# BrushBotComm_C3.net
KiCad netlist of a schematic drawn in EAGLE
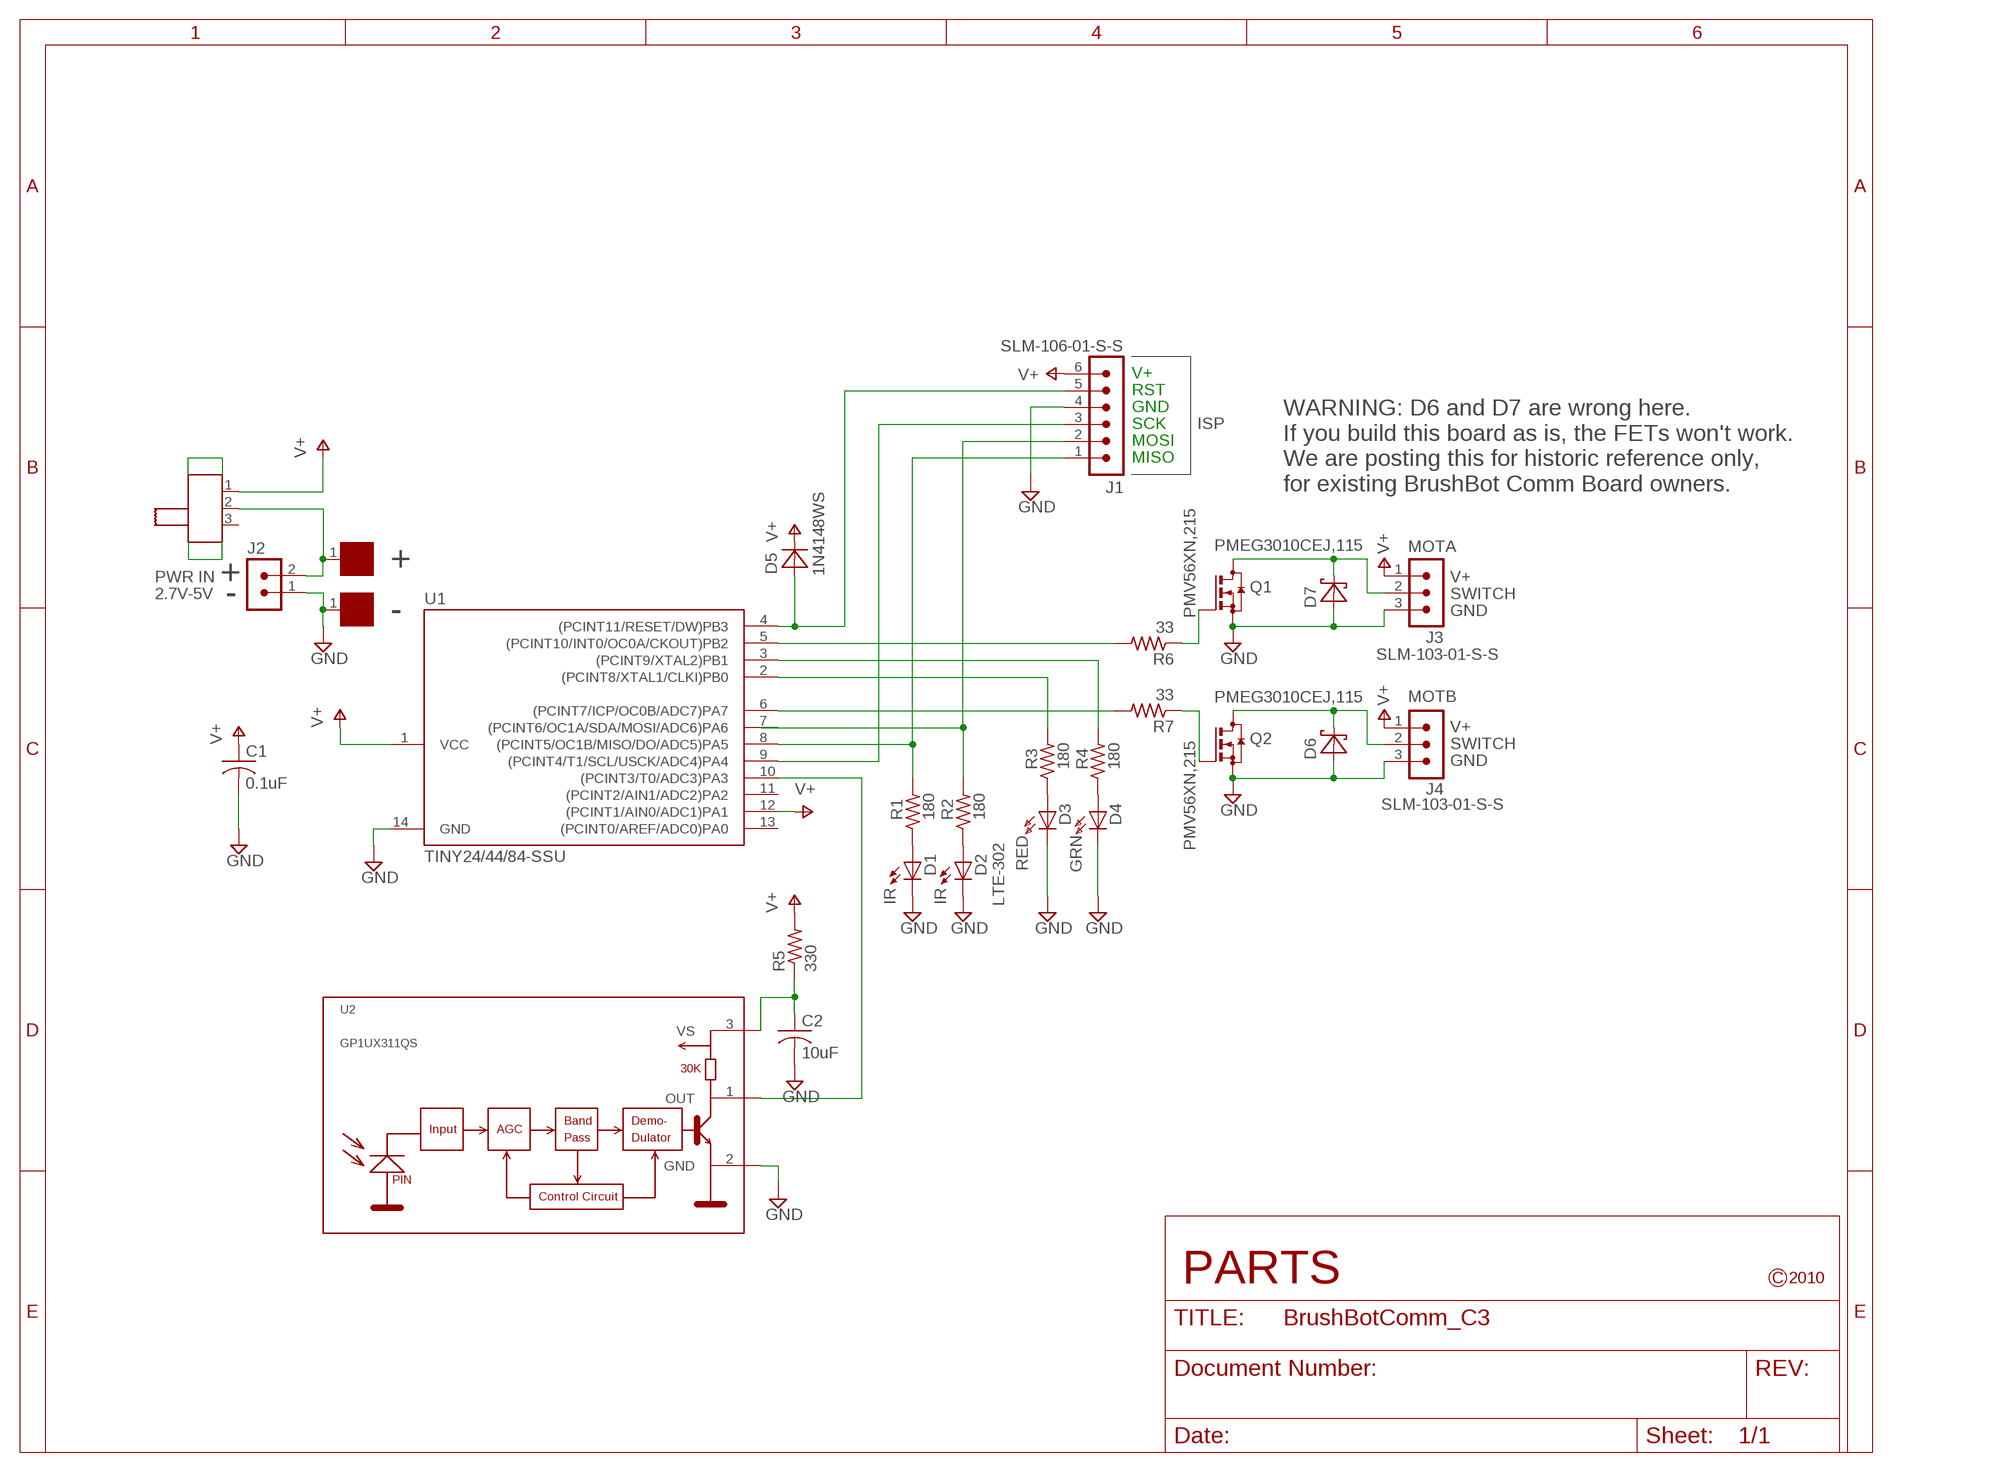
[diagram p0: schematic, sheet 1]

(export (version "E")
  (design (tool "Eeschema 10.0.6"))
  (components
    (comp (ref "+")
      (value "BATTERM4X4MM")
      (footprint "eagle-import:BATTERM")
      (libsource (lib "eagle-import") (part "BATTERM4X4MM"))
    )
    (comp (ref "-")
      (value "BATTERM4X4MM")
      (footprint "eagle-import:BATTERM")
      (libsource (lib "eagle-import") (part "BATTERM4X4MM"))
    )
    (comp (ref "C1")
      (value "0.1uF")
      (footprint "eagle-import:C0603")
      (libsource (lib "eagle-import") (part "C-USC0603"))
    )
    (comp (ref "C2")
      (value "10uF")
      (footprint "eagle-import:C1206")
      (libsource (lib "eagle-import") (part "C-USC1206"))
    )
    (comp (ref "D1")
      (value "LTE-302")
      (footprint "eagle-import:IRL80A")
      (libsource (lib "eagle-import") (part "LEDIRL80A"))
    )
    (comp (ref "D2")
      (value "LTE-302")
      (footprint "eagle-import:IRL80A")
      (libsource (lib "eagle-import") (part "LEDIRL80A"))
    )
    (comp (ref "D3")
      (value "RED")
      (footprint "eagle-import:LED603")
      (libsource (lib "eagle-import") (part "LED603"))
    )
    (comp (ref "D4")
      (value "GRN")
      (footprint "eagle-import:LED603")
      (libsource (lib "eagle-import") (part "LED603"))
    )
    (comp (ref "D5")
      (value "1N4148WS")
      (footprint "eagle-import:SOD323-R")
      (libsource (lib "eagle-import") (part "DIODE-SOD323-RE"))
    )
    (comp (ref "D6")
      (value "PMEG3010CEJ,115")
      (footprint "eagle-import:SOD323-R")
      (libsource (lib "eagle-import") (part "SCHOTTKYSOD323"))
    )
    (comp (ref "D7")
      (value "PMEG3010CEJ,115")
      (footprint "eagle-import:SOD323-R")
      (libsource (lib "eagle-import") (part "SCHOTTKYSOD323"))
    )
    (comp (ref "J1")
      (value "SLM-106-01-S-S")
      (footprint "eagle-import:MA06O-1-25")
      (libsource (lib "eagle-import") (part "MA06-1OCTPADS"))
    )
    (comp (ref "J2")
      (value "MA02-1OCTPADS")
      (footprint "eagle-import:MA02O-1")
      (libsource (lib "eagle-import") (part "MA02-1OCTPADS"))
    )
    (comp (ref "J3")
      (value "SLM-103-01-S-S")
      (footprint "eagle-import:MA03O-1-25")
      (libsource (lib "eagle-import") (part "MA03-1OCTPADS-25"))
    )
    (comp (ref "J4")
      (value "SLM-103-01-S-S")
      (footprint "eagle-import:MA03O-1-25")
      (libsource (lib "eagle-import") (part "MA03-1OCTPADS-25"))
    )
    (comp (ref "PWR")
      (value "SSSS811101")
      (footprint "eagle-import:SSSS8")
      (libsource (lib "eagle-import") (part "SSSS8"))
    )
    (comp (ref "Q1")
      (value "PMV56XN,215")
      (footprint "eagle-import:SOT23")
      (libsource (lib "eagle-import") (part "BSS123"))
    )
    (comp (ref "Q2")
      (value "PMV56XN,215")
      (footprint "eagle-import:SOT23")
      (libsource (lib "eagle-import") (part "BSS123"))
    )
    (comp (ref "R1")
      (value "180")
      (footprint "eagle-import:R0603")
      (libsource (lib "eagle-import") (part "R-US_R0603"))
    )
    (comp (ref "R2")
      (value "180")
      (footprint "eagle-import:R0603")
      (libsource (lib "eagle-import") (part "R-US_R0603"))
    )
    (comp (ref "R3")
      (value "180")
      (footprint "eagle-import:R0603")
      (libsource (lib "eagle-import") (part "R-US_R0603"))
    )
    (comp (ref "R4")
      (value "180")
      (footprint "eagle-import:R0603")
      (libsource (lib "eagle-import") (part "R-US_R0603"))
    )
    (comp (ref "R5")
      (value "330")
      (footprint "eagle-import:R0603")
      (libsource (lib "eagle-import") (part "R-US_R0603"))
    )
    (comp (ref "R6")
      (value "33")
      (footprint "eagle-import:R0603")
      (libsource (lib "eagle-import") (part "R-US_R0603"))
    )
    (comp (ref "R7")
      (value "33")
      (footprint "eagle-import:R0603")
      (libsource (lib "eagle-import") (part "R-US_R0603"))
    )
    (comp (ref "U1")
      (value "TINY24/44/84-SSU")
      (footprint "eagle-import:SOIC14")
      (libsource (lib "eagle-import") (part "TINY24/44/84-SSU"))
    )
    (comp (ref "U2")
      (value "GP1UX311QS")
      (footprint "eagle-import:TSOP348")
      (libsource (lib "eagle-import") (part "TSOP34830"))
    )
  )
  (nets
    (net (code "1") (name "GND") (class "Default")
      (node (ref "-") (pin "1") (pinfunction "1_1") (pintype "power_in"))
      (node (ref "C1") (pin "2") (pinfunction "2_2") (pintype "passive"))
      (node (ref "C2") (pin "2") (pinfunction "2_2") (pintype "passive"))
      (node (ref "D1") (pin "K") (pinfunction "C_K") (pintype "passive"))
      (node (ref "D2") (pin "K") (pinfunction "C_K") (pintype "passive"))
      (node (ref "D3") (pin "C") (pinfunction "C_C") (pintype "passive"))
      (node (ref "D4") (pin "C") (pinfunction "C_C") (pintype "passive"))
      (node (ref "D6") (pin "A") (pinfunction "A_A") (pintype "passive"))
      (node (ref "D7") (pin "A") (pinfunction "A_A") (pintype "passive"))
      (node (ref "J1") (pin "4") (pinfunction "4_4") (pintype "passive"))
      (node (ref "J2") (pin "1") (pinfunction "1_1") (pintype "passive"))
      (node (ref "J3") (pin "3") (pinfunction "3_3") (pintype "passive"))
      (node (ref "J4") (pin "3") (pinfunction "3_3") (pintype "passive"))
      (node (ref "Q1") (pin "2") (pinfunction "S_2") (pintype "passive"))
      (node (ref "Q2") (pin "2") (pinfunction "S_2") (pintype "passive"))
      (node (ref "U1") (pin "14") (pinfunction "GND_14") (pintype "power_in"))
      (node (ref "U2") (pin "2") (pinfunction "GND_2") (pintype "power_in"))
    )
    (net (code "2") (name "Net-(+-Pad1)") (class "Default")
      (node (ref "+") (pin "1") (pinfunction "1_1") (pintype "power_in"))
      (node (ref "J2") (pin "2") (pinfunction "2_2") (pintype "passive"))
      (node (ref "PWR") (pin "2") (pinfunction "2_2") (pintype "bidirectional"))
    )
    (net (code "3") (name "Net-(D1-PadA)") (class "Default")
      (node (ref "D1") (pin "A") (pinfunction "A_A") (pintype "passive"))
      (node (ref "R1") (pin "1") (pinfunction "1_1") (pintype "passive"))
    )
    (net (code "4") (name "Net-(D2-PadA)") (class "Default")
      (node (ref "D2") (pin "A") (pinfunction "A_A") (pintype "passive"))
      (node (ref "R2") (pin "1") (pinfunction "1_1") (pintype "passive"))
    )
    (net (code "5") (name "Net-(D3-PadA)") (class "Default")
      (node (ref "D3") (pin "A") (pinfunction "A_A") (pintype "passive"))
      (node (ref "R3") (pin "1") (pinfunction "1_1") (pintype "passive"))
    )
    (net (code "6") (name "Net-(D4-PadA)") (class "Default")
      (node (ref "D4") (pin "A") (pinfunction "A_A") (pintype "passive"))
      (node (ref "R4") (pin "1") (pinfunction "1_1") (pintype "passive"))
    )
    (net (code "7") (name "Net-(PWR-PadG1)") (class "Default")
      (node (ref "PWR") (pin "G1") (pinfunction "G1_G1") (pintype "bidirectional"))
      (node (ref "PWR") (pin "G2") (pinfunction "G2_G2") (pintype "bidirectional"))
    )
    (net (code "8") (name "Net-(PWR-PadG3)") (class "Default")
      (node (ref "PWR") (pin "G3") (pinfunction "G3_G3") (pintype "bidirectional"))
      (node (ref "PWR") (pin "G4") (pinfunction "G4_G4") (pintype "bidirectional"))
    )
    (net (code "9") (name "Net-(Q1-D)") (class "Default")
      (node (ref "D7") (pin "C") (pinfunction "C_C") (pintype "passive"))
      (node (ref "J3") (pin "2") (pinfunction "2_2") (pintype "passive"))
      (node (ref "Q1") (pin "3") (pinfunction "D_3") (pintype "passive"))
    )
    (net (code "10") (name "Net-(Q1-G)") (class "Default")
      (node (ref "Q1") (pin "1") (pinfunction "G_1") (pintype "passive"))
      (node (ref "R6") (pin "1") (pinfunction "1_1") (pintype "passive"))
    )
    (net (code "11") (name "Net-(Q2-D)") (class "Default")
      (node (ref "D6") (pin "C") (pinfunction "C_C") (pintype "passive"))
      (node (ref "J4") (pin "2") (pinfunction "2_2") (pintype "passive"))
      (node (ref "Q2") (pin "3") (pinfunction "D_3") (pintype "passive"))
    )
    (net (code "12") (name "Net-(Q2-G)") (class "Default")
      (node (ref "Q2") (pin "1") (pinfunction "G_1") (pintype "passive"))
      (node (ref "R7") (pin "1") (pinfunction "1_1") (pintype "passive"))
    )
    (net (code "13") (name "Net-(U1-(PCINT3{slash}T0{slash}ADC3)PA3)") (class "Default")
      (node (ref "U1") (pin "10") (pinfunction "(PCINT3/T0/ADC3)PA3_10") (pintype "bidirectional"))
      (node (ref "U2") (pin "1") (pinfunction "OUT_1") (pintype "output"))
    )
    (net (code "14") (name "Net-(U1-(PCINT4{slash}T1{slash}SCL{slash}USCK{slash}ADC4)PA4)") (class "Default")
      (node (ref "J1") (pin "3") (pinfunction "3_3") (pintype "passive"))
      (node (ref "U1") (pin "9") (pinfunction "(PCINT4/T1/SCL/USCK/ADC4)PA4_9") (pintype "bidirectional"))
    )
    (net (code "15") (name "Net-(U1-(PCINT5{slash}OC1B{slash}MISO{slash}DO{slash}ADC5)PA5)") (class "Default")
      (node (ref "J1") (pin "1") (pinfunction "1_1") (pintype "passive"))
      (node (ref "R1") (pin "2") (pinfunction "2_2") (pintype "passive"))
      (node (ref "U1") (pin "8") (pinfunction "(PCINT5/OC1B/MISO/DO/ADC5)PA5_8") (pintype "bidirectional"))
    )
    (net (code "16") (name "Net-(U1-(PCINT6{slash}OC1A{slash}SDA{slash}MOSI{slash}ADC6)PA6)") (class "Default")
      (node (ref "J1") (pin "2") (pinfunction "2_2") (pintype "passive"))
      (node (ref "R2") (pin "2") (pinfunction "2_2") (pintype "passive"))
      (node (ref "U1") (pin "7") (pinfunction "(PCINT6/OC1A/SDA/MOSI/ADC6)PA6_7") (pintype "bidirectional"))
    )
    (net (code "17") (name "Net-(U1-(PCINT7{slash}ICP{slash}OC0B{slash}ADC7)PA7)") (class "Default")
      (node (ref "R7") (pin "2") (pinfunction "2_2") (pintype "passive"))
      (node (ref "U1") (pin "6") (pinfunction "(PCINT7/ICP/OC0B/ADC7)PA7_6") (pintype "bidirectional"))
    )
    (net (code "18") (name "Net-(U1-(PCINT8{slash}XTAL1{slash}CLKI)PB0)") (class "Default")
      (node (ref "R3") (pin "2") (pinfunction "2_2") (pintype "passive"))
      (node (ref "U1") (pin "2") (pinfunction "(PCINT8/XTAL1/CLKI)PB0_2") (pintype "bidirectional"))
    )
    (net (code "19") (name "Net-(U1-(PCINT9{slash}XTAL2)PB1)") (class "Default")
      (node (ref "R4") (pin "2") (pinfunction "2_2") (pintype "passive"))
      (node (ref "U1") (pin "3") (pinfunction "(PCINT9/XTAL2)PB1_3") (pintype "bidirectional"))
    )
    (net (code "20") (name "Net-(U1-(PCINT10{slash}INT0{slash}OC0A{slash}CKOUT)PB2)") (class "Default")
      (node (ref "R6") (pin "2") (pinfunction "2_2") (pintype "passive"))
      (node (ref "U1") (pin "5") (pinfunction "(PCINT10/INT0/OC0A/CKOUT)PB2_5") (pintype "bidirectional"))
    )
    (net (code "21") (name "Net-(U1-(PCINT11{slash}RESET{slash}DW)PB3)") (class "Default")
      (node (ref "D5") (pin "A") (pinfunction "A_A") (pintype "passive"))
      (node (ref "J1") (pin "5") (pinfunction "5_5") (pintype "passive"))
      (node (ref "U1") (pin "4") (pinfunction "(PCINT11/RESET/DW)PB3_4") (pintype "bidirectional"))
    )
    (net (code "22") (name "Net-(U2-VS)") (class "Default")
      (node (ref "C2") (pin "1") (pinfunction "1_1") (pintype "passive"))
      (node (ref "R5") (pin "1") (pinfunction "1_1") (pintype "passive"))
      (node (ref "U2") (pin "3") (pinfunction "VS_3") (pintype "power_in"))
    )
    (net (code "23") (name "V+") (class "Default")
      (node (ref "C1") (pin "1") (pinfunction "1_1") (pintype "passive"))
      (node (ref "D5") (pin "C") (pinfunction "C_C") (pintype "passive"))
      (node (ref "J1") (pin "6") (pinfunction "6_6") (pintype "passive"))
      (node (ref "J3") (pin "1") (pinfunction "1_1") (pintype "passive"))
      (node (ref "J4") (pin "1") (pinfunction "1_1") (pintype "passive"))
      (node (ref "PWR") (pin "1") (pinfunction "1_1") (pintype "bidirectional"))
      (node (ref "R5") (pin "2") (pinfunction "2_2") (pintype "passive"))
      (node (ref "U1") (pin "1") (pinfunction "VCC_1") (pintype "power_in"))
      (node (ref "U1") (pin "12") (pinfunction "(PCINT1/AIN0/ADC1)PA1_12") (pintype "bidirectional"))
    )
    (net (code "24") (name "unconnected-(PWR-Pad3)") (class "Default")
      (node (ref "PWR") (pin "3") (pinfunction "3_3") (pintype "bidirectional"))
    )
    (net (code "25") (name "unconnected-(U1-(PCINT0{slash}AREF{slash}ADC0)PA0-Pad13)") (class "Default")
      (node (ref "U1") (pin "13") (pinfunction "(PCINT0/AREF/ADC0)PA0_13") (pintype "bidirectional"))
    )
    (net (code "26") (name "unconnected-(U1-(PCINT2{slash}AIN1{slash}ADC2)PA2-Pad11)") (class "Default")
      (node (ref "U1") (pin "11") (pinfunction "(PCINT2/AIN1/ADC2)PA2_11") (pintype "bidirectional"))
    )
  )
)
